# v2.net
KiCad netlist of a schematic drawn in EAGLE
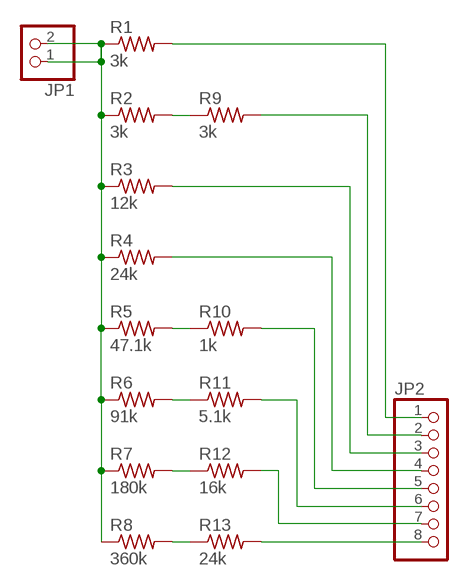
[diagram p0: schematic, sheet 1]

(export (version "E")
  (design (tool "Eeschema 10.0.6"))
  (components
    (comp (ref "JP1")
      (value "PINHD-1X2")
      (footprint "eagle-import:1X02")
      (libsource (lib "eagle-import") (part "PINHD-1X2"))
    )
    (comp (ref "JP2")
      (value "PINHD-1X8")
      (footprint "eagle-import:1X08")
      (libsource (lib "eagle-import") (part "PINHD-1X8"))
    )
    (comp (ref "R1")
      (value "3k")
      (footprint "eagle-import:0309_10")
      (libsource (lib "eagle-import") (part "R-US_0309/10"))
    )
    (comp (ref "R2")
      (value "3k")
      (footprint "eagle-import:0309_10")
      (libsource (lib "eagle-import") (part "R-US_0309/10"))
    )
    (comp (ref "R3")
      (value "12k")
      (footprint "eagle-import:0309_10")
      (libsource (lib "eagle-import") (part "R-US_0309/10"))
    )
    (comp (ref "R4")
      (value "24k")
      (footprint "eagle-import:0309_10")
      (libsource (lib "eagle-import") (part "R-US_0309/10"))
    )
    (comp (ref "R5")
      (value "47.1k")
      (footprint "eagle-import:0309_10")
      (libsource (lib "eagle-import") (part "R-US_0309/10"))
    )
    (comp (ref "R6")
      (value "91k")
      (footprint "eagle-import:0309_10")
      (libsource (lib "eagle-import") (part "R-US_0309/10"))
    )
    (comp (ref "R7")
      (value "180k")
      (footprint "eagle-import:0309_10")
      (libsource (lib "eagle-import") (part "R-US_0309/10"))
    )
    (comp (ref "R8")
      (value "360k")
      (footprint "eagle-import:0309_10")
      (libsource (lib "eagle-import") (part "R-US_0309/10"))
    )
    (comp (ref "R9")
      (value "3k")
      (footprint "eagle-import:0309_10")
      (libsource (lib "eagle-import") (part "R-US_0309/10"))
    )
    (comp (ref "R10")
      (value "1k")
      (footprint "eagle-import:0309_10")
      (libsource (lib "eagle-import") (part "R-US_0309/10"))
    )
    (comp (ref "R11")
      (value "5.1k")
      (footprint "eagle-import:0309_10")
      (libsource (lib "eagle-import") (part "R-US_0309/10"))
    )
    (comp (ref "R12")
      (value "16k")
      (footprint "eagle-import:0309_10")
      (libsource (lib "eagle-import") (part "R-US_0309/10"))
    )
    (comp (ref "R13")
      (value "24k")
      (footprint "eagle-import:0309_10")
      (libsource (lib "eagle-import") (part "R-US_0309/10"))
    )
  )
  (nets
    (net (code "1") (name "Net-(JP1-Pad1)") (class "Default")
      (node (ref "JP1") (pin "1") (pinfunction "1_1") (pintype "passive"))
      (node (ref "JP1") (pin "2") (pinfunction "2_2") (pintype "passive"))
      (node (ref "R1") (pin "1") (pinfunction "1_1") (pintype "passive"))
      (node (ref "R2") (pin "1") (pinfunction "1_1") (pintype "passive"))
      (node (ref "R3") (pin "1") (pinfunction "1_1") (pintype "passive"))
      (node (ref "R4") (pin "1") (pinfunction "1_1") (pintype "passive"))
      (node (ref "R5") (pin "1") (pinfunction "1_1") (pintype "passive"))
      (node (ref "R6") (pin "1") (pinfunction "1_1") (pintype "passive"))
      (node (ref "R7") (pin "1") (pinfunction "1_1") (pintype "passive"))
      (node (ref "R8") (pin "1") (pinfunction "1_1") (pintype "passive"))
    )
    (net (code "2") (name "Net-(JP2-Pad1)") (class "Default")
      (node (ref "JP2") (pin "1") (pinfunction "1_1") (pintype "passive"))
      (node (ref "R1") (pin "2") (pinfunction "2_2") (pintype "passive"))
    )
    (net (code "3") (name "Net-(JP2-Pad2)") (class "Default")
      (node (ref "JP2") (pin "2") (pinfunction "2_2") (pintype "passive"))
      (node (ref "R9") (pin "2") (pinfunction "2_2") (pintype "passive"))
    )
    (net (code "4") (name "Net-(JP2-Pad3)") (class "Default")
      (node (ref "JP2") (pin "3") (pinfunction "3_3") (pintype "passive"))
      (node (ref "R3") (pin "2") (pinfunction "2_2") (pintype "passive"))
    )
    (net (code "5") (name "Net-(JP2-Pad4)") (class "Default")
      (node (ref "JP2") (pin "4") (pinfunction "4_4") (pintype "passive"))
      (node (ref "R4") (pin "2") (pinfunction "2_2") (pintype "passive"))
    )
    (net (code "6") (name "Net-(JP2-Pad5)") (class "Default")
      (node (ref "JP2") (pin "5") (pinfunction "5_5") (pintype "passive"))
      (node (ref "R10") (pin "2") (pinfunction "2_2") (pintype "passive"))
    )
    (net (code "7") (name "Net-(JP2-Pad6)") (class "Default")
      (node (ref "JP2") (pin "6") (pinfunction "6_6") (pintype "passive"))
      (node (ref "R11") (pin "2") (pinfunction "2_2") (pintype "passive"))
    )
    (net (code "8") (name "Net-(JP2-Pad7)") (class "Default")
      (node (ref "JP2") (pin "7") (pinfunction "7_7") (pintype "passive"))
      (node (ref "R12") (pin "2") (pinfunction "2_2") (pintype "passive"))
    )
    (net (code "9") (name "Net-(JP2-Pad8)") (class "Default")
      (node (ref "JP2") (pin "8") (pinfunction "8_8") (pintype "passive"))
      (node (ref "R13") (pin "2") (pinfunction "2_2") (pintype "passive"))
    )
    (net (code "10") (name "Net-(R2-Pad2)") (class "Default")
      (node (ref "R2") (pin "2") (pinfunction "2_2") (pintype "passive"))
      (node (ref "R9") (pin "1") (pinfunction "1_1") (pintype "passive"))
    )
    (net (code "11") (name "Net-(R10-Pad1)") (class "Default")
      (node (ref "R10") (pin "1") (pinfunction "1_1") (pintype "passive"))
      (node (ref "R5") (pin "2") (pinfunction "2_2") (pintype "passive"))
    )
    (net (code "12") (name "Net-(R11-Pad1)") (class "Default")
      (node (ref "R11") (pin "1") (pinfunction "1_1") (pintype "passive"))
      (node (ref "R6") (pin "2") (pinfunction "2_2") (pintype "passive"))
    )
    (net (code "13") (name "Net-(R12-Pad1)") (class "Default")
      (node (ref "R12") (pin "1") (pinfunction "1_1") (pintype "passive"))
      (node (ref "R7") (pin "2") (pinfunction "2_2") (pintype "passive"))
    )
    (net (code "14") (name "Net-(R13-Pad1)") (class "Default")
      (node (ref "R13") (pin "1") (pinfunction "1_1") (pintype "passive"))
      (node (ref "R8") (pin "2") (pinfunction "2_2") (pintype "passive"))
    )
  )
)
